# Xbee_circuit.net
KiCad netlist of a schematic drawn in EAGLE
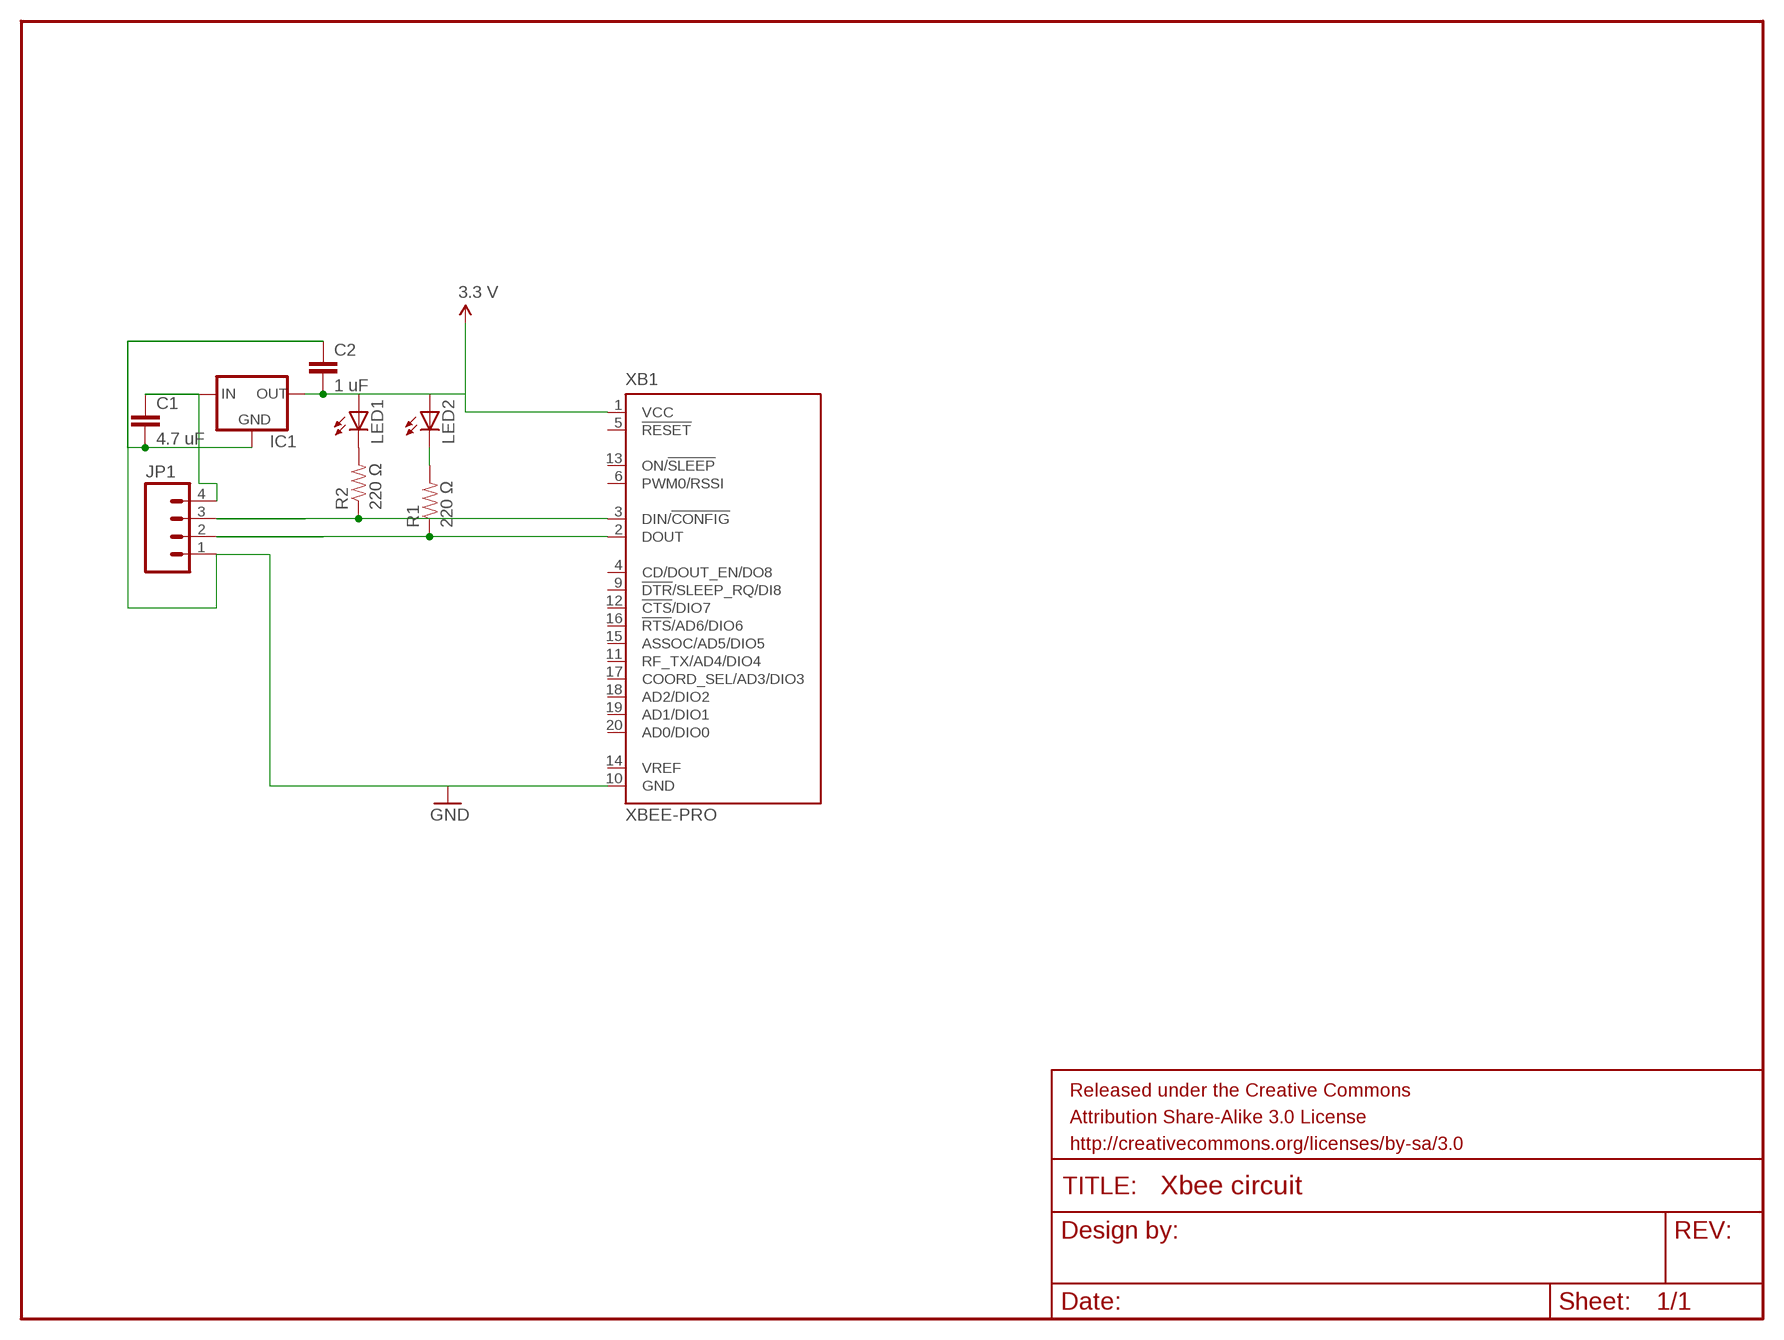
[diagram p0: schematic, sheet 1]

(export (version "E")
  (design (tool "Eeschema 10.0.6"))
  (components
    (comp (ref "C1")
      (value "4.7 uF")
      (footprint "eagle-import:0805")
      (libsource (lib "eagle-import") (part "CAP0805"))
    )
    (comp (ref "C2")
      (value "1 uF")
      (footprint "eagle-import:0805")
      (libsource (lib "eagle-import") (part "CAP0805"))
    )
    (comp (ref "FRAME1")
      (value "FRAME-LETTER")
      (footprint "eagle-import:CREATIVE_COMMONS")
      (libsource (lib "eagle-import") (part "FRAME-LETTER"))
    )
    (comp (ref "IC1")
      (value "V_REG_78XXSINK")
      (footprint "eagle-import:TO220-IGO")
      (libsource (lib "eagle-import") (part "V_REG_78XXSINK"))
    )
    (comp (ref "JP1")
      (value "M04LOCK")
      (footprint "eagle-import:1X04_LOCK")
      (libsource (lib "eagle-import") (part "M04LOCK"))
    )
    (comp (ref "LED1")
      (value "LED5MM")
      (footprint "eagle-import:LED5MM")
      (libsource (lib "eagle-import") (part "LED5MM"))
    )
    (comp (ref "LED2")
      (value "LED5MM")
      (footprint "eagle-import:LED5MM")
      (libsource (lib "eagle-import") (part "LED5MM"))
    )
    (comp (ref "R1")
      (value "220 Ω")
      (footprint "eagle-import:0805")
      (libsource (lib "eagle-import") (part "RESISTOR0805-RES"))
    )
    (comp (ref "R2")
      (value "220 Ω")
      (footprint "eagle-import:0805")
      (libsource (lib "eagle-import") (part "RESISTOR0805-RES"))
    )
    (comp (ref "XB1")
      (value "XBEE-PRO")
      (footprint "eagle-import:XBEE-PRO")
      (fields (field (name "MPN") "XBP24-AWI-001"))
      (libsource (lib "eagle-import") (part "XBEE-PRO"))
    )
  )
  (nets
    (net (code "1") (name "3.3 V") (class "Default")
      (node (ref "C2") (pin "2") (pinfunction "2_2") (pintype "passive"))
      (node (ref "IC1") (pin "OUT") (pinfunction "OUT_OUT") (pintype "output"))
      (node (ref "LED1") (pin "A") (pinfunction "A_A") (pintype "passive"))
      (node (ref "LED2") (pin "A") (pinfunction "A_A") (pintype "passive"))
      (node (ref "XB1") (pin "1") (pinfunction "VCC_1") (pintype "power_in"))
    )
    (net (code "2") (name "GND") (class "Default")
      (node (ref "C1") (pin "2") (pinfunction "2_2") (pintype "passive"))
      (node (ref "C2") (pin "1") (pinfunction "1_1") (pintype "passive"))
      (node (ref "IC1") (pin "GND") (pinfunction "GND_GND") (pintype "input"))
      (node (ref "JP1") (pin "1") (pinfunction "1_1") (pintype "passive"))
      (node (ref "XB1") (pin "10") (pinfunction "GND_10") (pintype "power_in"))
    )
    (net (code "3") (name "Net-(C1-Pad1)") (class "Default")
      (node (ref "C1") (pin "1") (pinfunction "1_1") (pintype "passive"))
      (node (ref "IC1") (pin "IN") (pinfunction "IN_IN") (pintype "input"))
      (node (ref "JP1") (pin "4") (pinfunction "4_4") (pintype "passive"))
    )
    (net (code "4") (name "Net-(LED1-C)") (class "Default")
      (node (ref "LED1") (pin "K") (pinfunction "C_K") (pintype "passive"))
      (node (ref "R2") (pin "2") (pinfunction "2_2") (pintype "passive"))
    )
    (net (code "5") (name "Net-(LED2-C)") (class "Default")
      (node (ref "LED2") (pin "K") (pinfunction "C_K") (pintype "passive"))
      (node (ref "R1") (pin "2") (pinfunction "2_2") (pintype "passive"))
    )
    (net (code "6") (name "Net-(XB1-DIN{slash}~{CONFIG})") (class "Default")
      (node (ref "JP1") (pin "3") (pinfunction "3_3") (pintype "passive"))
      (node (ref "R2") (pin "1") (pinfunction "1_1") (pintype "passive"))
      (node (ref "XB1") (pin "3") (pinfunction "DIN/~{CONFIG}_3") (pintype "input"))
    )
    (net (code "7") (name "Net-(XB1-DOUT)") (class "Default")
      (node (ref "JP1") (pin "2") (pinfunction "2_2") (pintype "passive"))
      (node (ref "R1") (pin "1") (pinfunction "1_1") (pintype "passive"))
      (node (ref "XB1") (pin "2") (pinfunction "DOUT_2") (pintype "output"))
    )
    (net (code "8") (name "unconnected-(XB1-AD0{slash}DIO0-Pad20)") (class "Default")
      (node (ref "XB1") (pin "20") (pinfunction "AD0/DIO0_20") (pintype "bidirectional"))
    )
    (net (code "9") (name "unconnected-(XB1-AD1{slash}DIO1-Pad19)") (class "Default")
      (node (ref "XB1") (pin "19") (pinfunction "AD1/DIO1_19") (pintype "bidirectional"))
    )
    (net (code "10") (name "unconnected-(XB1-AD2{slash}DIO2-Pad18)") (class "Default")
      (node (ref "XB1") (pin "18") (pinfunction "AD2/DIO2_18") (pintype "bidirectional"))
    )
    (net (code "11") (name "unconnected-(XB1-ASSOC{slash}AD5{slash}DIO5-Pad15)") (class "Default")
      (node (ref "XB1") (pin "15") (pinfunction "ASSOC/AD5/DIO5_15") (pintype "bidirectional"))
    )
    (net (code "12") (name "unconnected-(XB1-CD{slash}DOUT_EN{slash}DO8-Pad4)") (class "Default")
      (node (ref "XB1") (pin "4") (pinfunction "CD/DOUT_EN/DO8_4") (pintype "output"))
    )
    (net (code "13") (name "unconnected-(XB1-COORD_SEL{slash}AD3{slash}DIO3-Pad17)") (class "Default")
      (node (ref "XB1") (pin "17") (pinfunction "COORD_SEL/AD3/DIO3_17") (pintype "bidirectional"))
    )
    (net (code "14") (name "unconnected-(XB1-ON{slash}~{SLEEP}-Pad13)") (class "Default")
      (node (ref "XB1") (pin "13") (pinfunction "ON/~{SLEEP}_13") (pintype "output"))
    )
    (net (code "15") (name "unconnected-(XB1-PWM0{slash}RSSI-Pad6)") (class "Default")
      (node (ref "XB1") (pin "6") (pinfunction "PWM0/RSSI_6") (pintype "output"))
    )
    (net (code "16") (name "unconnected-(XB1-RF_TX{slash}AD4{slash}DIO4-Pad11)") (class "Default")
      (node (ref "XB1") (pin "11") (pinfunction "RF_TX/AD4/DIO4_11") (pintype "bidirectional"))
    )
    (net (code "17") (name "unconnected-(XB1-VREF-Pad14)") (class "Default")
      (node (ref "XB1") (pin "14") (pinfunction "VREF_14") (pintype "input"))
    )
    (net (code "18") (name "unconnected-(XB1-~{CTS}{slash}DIO7-Pad12)") (class "Default")
      (node (ref "XB1") (pin "12") (pinfunction "~{CTS}/DIO7_12") (pintype "bidirectional"))
    )
    (net (code "19") (name "unconnected-(XB1-~{DTR}{slash}SLEEP_RQ{slash}DI8-Pad9)") (class "Default")
      (node (ref "XB1") (pin "9") (pinfunction "~{DTR}/SLEEP_RQ/DI8_9") (pintype "bidirectional"))
    )
    (net (code "20") (name "unconnected-(XB1-~{RESET}-Pad5)") (class "Default")
      (node (ref "XB1") (pin "5") (pinfunction "~{RESET}_5") (pintype "input"))
    )
    (net (code "21") (name "unconnected-(XB1-~{RTS}{slash}AD6{slash}DIO6-Pad16)") (class "Default")
      (node (ref "XB1") (pin "16") (pinfunction "~{RTS}/AD6/DIO6_16") (pintype "bidirectional"))
    )
  )
)
